# moduleV08.net
KiCad netlist of a schematic drawn in EAGLE
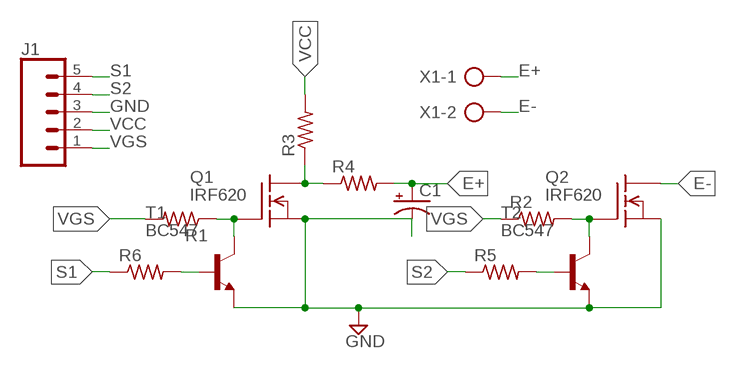
[diagram p0: schematic, sheet 1]

(export (version "E")
  (design (tool "Eeschema 10.0.6"))
  (components
    (comp (ref "C1")
      (value "CAPACITOR-PE3.5-8")
      (footprint "eagle-import:E3,5-8")
      (libsource (lib "eagle-import") (part "CAPACITOR-PE3.5-8"))
    )
    (comp (ref "J1")
      (value "CONN_05")
      (footprint "eagle-import:1X05")
      (libsource (lib "eagle-import") (part "CONN_05"))
    )
    (comp (ref "Q1")
      (value "IRF620")
      (footprint "eagle-import:TO220")
      (libsource (lib "eagle-import") (part "IRF620"))
    )
    (comp (ref "Q2")
      (value "IRF620")
      (footprint "eagle-import:TO220")
      (libsource (lib "eagle-import") (part "IRF620"))
    )
    (comp (ref "R1")
      (value "R-US_0204/7")
      (footprint "eagle-import:0204_7")
      (libsource (lib "eagle-import") (part "R-US_0204/7"))
    )
    (comp (ref "R2")
      (value "R-US_0204/7")
      (footprint "eagle-import:0204_7")
      (libsource (lib "eagle-import") (part "R-US_0204/7"))
    )
    (comp (ref "R3")
      (value "R-US_0204/7")
      (footprint "eagle-import:0204_7")
      (libsource (lib "eagle-import") (part "R-US_0204/7"))
    )
    (comp (ref "R4")
      (value "R-US_0204/7")
      (footprint "eagle-import:0204_7")
      (libsource (lib "eagle-import") (part "R-US_0204/7"))
    )
    (comp (ref "R5")
      (value "R-US_0204/7")
      (footprint "eagle-import:0204_7")
      (libsource (lib "eagle-import") (part "R-US_0204/7"))
    )
    (comp (ref "R6")
      (value "R-US_0204/7")
      (footprint "eagle-import:0204_7")
      (libsource (lib "eagle-import") (part "R-US_0204/7"))
    )
    (comp (ref "T1")
      (value "BC547")
      (footprint "eagle-import:TO92")
      (libsource (lib "eagle-import") (part "BC547"))
    )
    (comp (ref "T2")
      (value "BC547")
      (footprint "eagle-import:TO92")
      (libsource (lib "eagle-import") (part "BC547"))
    )
    (comp (ref "X1")
      (value "AK500/2-H")
      (footprint "eagle-import:AK500_2-H")
      (libsource (lib "eagle-import") (part "AK500/2-H"))
    )
  )
  (nets
    (net (code "1") (name "E+") (class "Default")
      (node (ref "C1") (pin "+") (pinfunction "+_+") (pintype "passive"))
      (node (ref "R4") (pin "2") (pinfunction "2_2") (pintype "passive"))
      (node (ref "X1") (pin "1") (pinfunction "KL_1") (pintype "passive"))
    )
    (net (code "2") (name "E-") (class "Default")
      (node (ref "Q2") (pin "2") (pinfunction "D_2") (pintype "passive"))
      (node (ref "X1") (pin "2") (pinfunction "KL_2") (pintype "passive"))
    )
    (net (code "3") (name "GND") (class "Default")
      (node (ref "C1") (pin "-") (pinfunction "-_-") (pintype "passive"))
      (node (ref "J1") (pin "3") (pinfunction "3_3") (pintype "passive"))
      (node (ref "Q1") (pin "3") (pinfunction "S_3") (pintype "passive"))
      (node (ref "Q2") (pin "3") (pinfunction "S_3") (pintype "passive"))
      (node (ref "T1") (pin "1") (pinfunction "E_1") (pintype "passive"))
      (node (ref "T2") (pin "1") (pinfunction "E_1") (pintype "passive"))
    )
    (net (code "4") (name "Net-(Q1-D)") (class "Default")
      (node (ref "Q1") (pin "2") (pinfunction "D_2") (pintype "passive"))
      (node (ref "R3") (pin "1") (pinfunction "1_1") (pintype "passive"))
      (node (ref "R4") (pin "1") (pinfunction "1_1") (pintype "passive"))
    )
    (net (code "5") (name "Net-(Q1-G)") (class "Default")
      (node (ref "Q1") (pin "1") (pinfunction "G_1") (pintype "passive"))
      (node (ref "R1") (pin "1") (pinfunction "1_1") (pintype "passive"))
      (node (ref "T1") (pin "3") (pinfunction "C_3") (pintype "passive"))
    )
    (net (code "6") (name "Net-(Q2-G)") (class "Default")
      (node (ref "Q2") (pin "1") (pinfunction "G_1") (pintype "passive"))
      (node (ref "R2") (pin "2") (pinfunction "2_2") (pintype "passive"))
      (node (ref "T2") (pin "3") (pinfunction "C_3") (pintype "passive"))
    )
    (net (code "7") (name "Net-(T1-B)") (class "Default")
      (node (ref "R6") (pin "2") (pinfunction "2_2") (pintype "passive"))
      (node (ref "T1") (pin "2") (pinfunction "B_2") (pintype "passive"))
    )
    (net (code "8") (name "Net-(T2-B)") (class "Default")
      (node (ref "R5") (pin "2") (pinfunction "2_2") (pintype "passive"))
      (node (ref "T2") (pin "2") (pinfunction "B_2") (pintype "passive"))
    )
    (net (code "9") (name "S1") (class "Default")
      (node (ref "J1") (pin "5") (pinfunction "5_5") (pintype "passive"))
      (node (ref "R6") (pin "1") (pinfunction "1_1") (pintype "passive"))
    )
    (net (code "10") (name "S2") (class "Default")
      (node (ref "J1") (pin "4") (pinfunction "4_4") (pintype "passive"))
      (node (ref "R5") (pin "1") (pinfunction "1_1") (pintype "passive"))
    )
    (net (code "11") (name "VCC") (class "Default")
      (node (ref "J1") (pin "2") (pinfunction "2_2") (pintype "passive"))
      (node (ref "R3") (pin "2") (pinfunction "2_2") (pintype "passive"))
    )
    (net (code "12") (name "VGS") (class "Default")
      (node (ref "J1") (pin "1") (pinfunction "1_1") (pintype "passive"))
      (node (ref "R1") (pin "2") (pinfunction "2_2") (pintype "passive"))
      (node (ref "R2") (pin "1") (pinfunction "1_1") (pintype "passive"))
    )
  )
)
